# ADC_MCP3008.net
KiCad netlist of a schematic drawn in Altium Designer
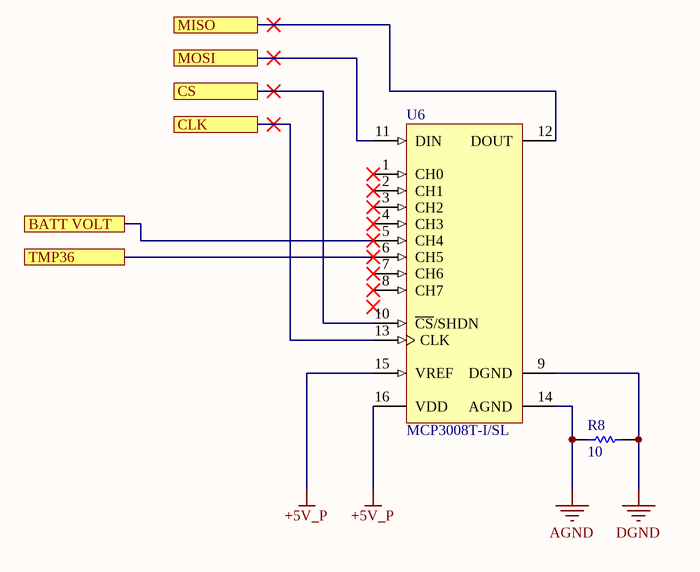
[diagram p0: ADC_MCP3008.SchDoc]

(export (version "E")
  (design (tool "Eeschema 10.0.6"))
  (components
    (comp (ref "R8")
      (value "10")
      (footprint "RESC3216X60X45ML10T20")
      (fields (field (name "MANUFACTURER") "Vishay Dale") (field (name "PART NUMBER") "CRCW120610R0FKEA"))
      (libsource (lib "Altium Content Vault") (part "RES"))
    )
    (comp (ref "U6")
      (value "MCP3008T-I/SL")
      (footprint "SOIC-SL16_N")
      (libsource (lib "Altium Content Vault") (part "CON-ADC-MCP3008-16"))
    )
  )
  (nets
    (net (code "1") (name "+5V_P") (class "Default")
      (node (ref "U6") (pin "15") (pinfunction "VREF_15") (pintype "input"))
      (node (ref "U6") (pin "16") (pinfunction "VDD_16") (pintype "power_in"))
    )
    (net (code "2") (name "/BATT VOLT") (class "Default")
      (node (ref "U6") (pin "5") (pinfunction "CH4_5") (pintype "input+no_connect"))
    )
    (net (code "3") (name "/CLK") (class "Default")
      (node (ref "U6") (pin "13") (pinfunction "CLK_13") (pintype "input"))
    )
    (net (code "4") (name "/CS") (class "Default")
      (node (ref "U6") (pin "10") (pinfunction "~{CS}/SHDN_10") (pintype "input"))
    )
    (net (code "5") (name "/MISO") (class "Default")
      (node (ref "U6") (pin "12") (pinfunction "DOUT_12") (pintype "tri_state"))
    )
    (net (code "6") (name "/MOSI") (class "Default")
      (node (ref "U6") (pin "11") (pinfunction "DIN_11") (pintype "input"))
    )
    (net (code "7") (name "/TMP36") (class "Default")
      (node (ref "U6") (pin "6") (pinfunction "CH5_6") (pintype "input+no_connect"))
    )
    (net (code "8") (name "AGND") (class "Default")
      (node (ref "R8") (pin "1") (pinfunction "1_1") (pintype "passive"))
      (node (ref "U6") (pin "14") (pinfunction "AGND_14") (pintype "power_in"))
    )
    (net (code "9") (name "DGND") (class "Default")
      (node (ref "R8") (pin "2") (pinfunction "2_2") (pintype "passive"))
      (node (ref "U6") (pin "9") (pinfunction "DGND_9") (pintype "power_in"))
    )
    (net (code "10") (name "unconnected-(U6-CH0-Pad1)") (class "Default")
      (node (ref "U6") (pin "1") (pinfunction "CH0_1") (pintype "input+no_connect"))
    )
    (net (code "11") (name "unconnected-(U6-CH1-Pad2)") (class "Default")
      (node (ref "U6") (pin "2") (pinfunction "CH1_2") (pintype "input+no_connect"))
    )
    (net (code "12") (name "unconnected-(U6-CH2-Pad3)") (class "Default")
      (node (ref "U6") (pin "3") (pinfunction "CH2_3") (pintype "input+no_connect"))
    )
    (net (code "13") (name "unconnected-(U6-CH3-Pad4)") (class "Default")
      (node (ref "U6") (pin "4") (pinfunction "CH3_4") (pintype "input+no_connect"))
    )
    (net (code "14") (name "unconnected-(U6-CH6-Pad7)") (class "Default")
      (node (ref "U6") (pin "7") (pinfunction "CH6_7") (pintype "input+no_connect"))
    )
    (net (code "15") (name "unconnected-(U6-CH7-Pad8)") (class "Default")
      (node (ref "U6") (pin "8") (pinfunction "CH7_8") (pintype "input+no_connect"))
    )
  )
)
